# MainCyclomotion.net
KiCad netlist of a schematic drawn in Altium Designer
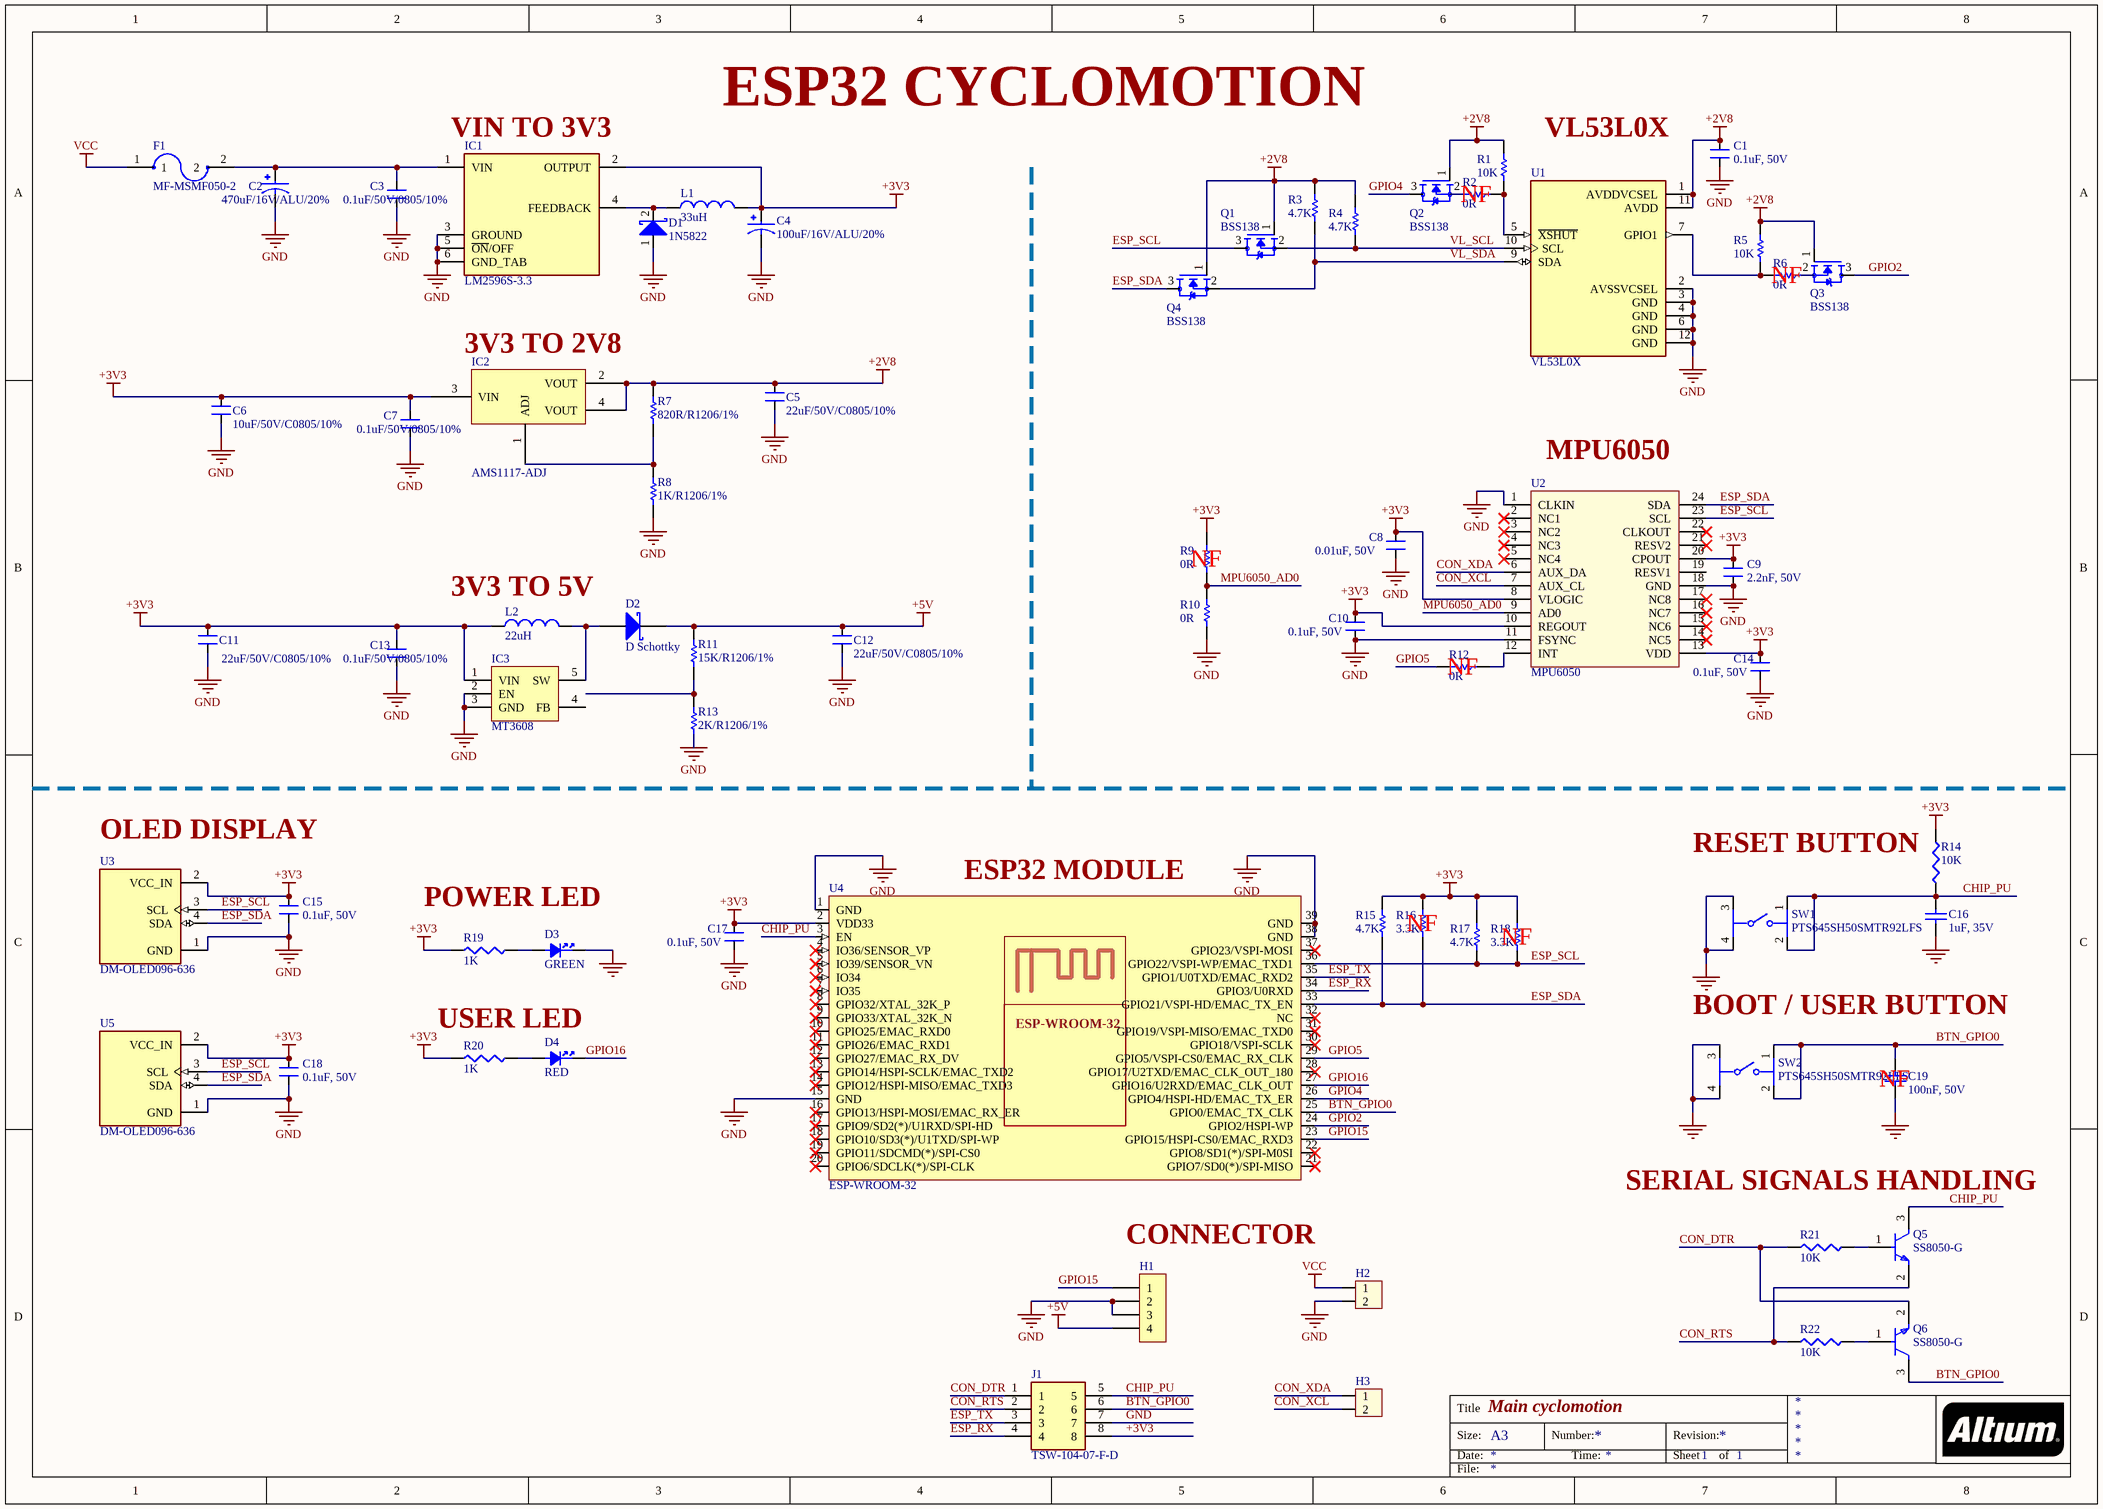
[diagram p0: MainCyclomotion.SchDoc]

(export (version "E")
  (design (tool "Eeschema 10.0.6"))
  (components
    (comp (ref "C1")
      (value "0.1uF, 50V")
      (footprint "CAP_CERA_C2012(CC0805INCH)")
      (description "CERAMIC CAP 0805")
      (libsource (lib "LPSON") (part "CAP CERA 0805"))
    )
    (comp (ref "C2")
      (value "470uF/16V/ALU/20%")
      (footprint "Cap_ALU_D_SMD")
      (libsource (lib "Schlib1") (part "Cap_ALU_D_SMD"))
    )
    (comp (ref "C3")
      (value "0.1uF/50V/0805/10%")
      (footprint "CAP_CERA_C2012(CC0805INCH)")
      (description "CERAMIC CAP 0805")
      (libsource (lib "LPSON") (part "CAP CERA 0805"))
    )
    (comp (ref "C4")
      (value "100uF/16V/ALU/20%")
      (footprint "Cap_ALU_E_SMD")
      (libsource (lib "Schlib1") (part "Cap_ALU_E_SMD"))
    )
    (comp (ref "C5")
      (value "22uF/50V/C0805/10%")
      (footprint "CAP_CERA_C2012(CC0805INCH)")
      (description "CERAMIC CAP 0805")
      (libsource (lib "Cyclomotion") (part "CAP CERA 0805"))
    )
    (comp (ref "C6")
      (value "10uF/50V/C0805/10%")
      (footprint "CAP_CERA_C2012(CC0805INCH)")
      (description "CERAMIC CAP 0805")
      (libsource (lib "Cyclomotion") (part "CAP CERA 0805"))
    )
    (comp (ref "C7")
      (value "0.1uF/50V/0805/10%")
      (footprint "CAP_CERA_C2012(CC0805INCH)")
      (description "CERAMIC CAP 0805")
      (libsource (lib "LPSON") (part "CAP CERA 0805"))
    )
    (comp (ref "C8")
      (value "0.01uF, 50V")
      (footprint "CAP_CERA_C2012(CC0805INCH)")
      (description "CERAMIC CAP 0805")
      (libsource (lib "LPSON") (part "CAP CERA 0805"))
    )
    (comp (ref "C9")
      (value "2.2nF, 50V")
      (footprint "CAP_CERA_C2012(CC0805INCH)")
      (description "CERAMIC CAP 0805")
      (libsource (lib "LPSON") (part "CAP CERA 0805"))
    )
    (comp (ref "C10")
      (value "0.1uF, 50V")
      (footprint "CAP_CERA_C2012(CC0805INCH)")
      (description "CERAMIC CAP 0805")
      (libsource (lib "LPSON") (part "CAP CERA 0805"))
    )
    (comp (ref "C11")
      (value "22uF/50V/C0805/10%")
      (footprint "CAP_CERA_C2012(CC0805INCH)")
      (description "CERAMIC CAP 0805")
      (libsource (lib "Cyclomotion") (part "CAP CERA 0805"))
    )
    (comp (ref "C12")
      (value "22uF/50V/C0805/10%")
      (footprint "CAP_CERA_C2012(CC0805INCH)")
      (description "CERAMIC CAP 0805")
      (libsource (lib "Cyclomotion") (part "CAP CERA 0805"))
    )
    (comp (ref "C13")
      (value "0.1uF/50V/0805/10%")
      (footprint "CAP_CERA_C2012(CC0805INCH)")
      (description "CERAMIC CAP 0805")
      (libsource (lib "LPSON") (part "CAP CERA 0805"))
    )
    (comp (ref "C14")
      (value "0.1uF, 50V")
      (footprint "CAP_CERA_C2012(CC0805INCH)")
      (description "CERAMIC CAP 0805")
      (libsource (lib "LPSON") (part "CAP CERA 0805"))
    )
    (comp (ref "C15")
      (value "0.1uF, 50V")
      (footprint "CAP_CERA_C2012(CC0805INCH)")
      (description "CERAMIC CAP 0805")
      (libsource (lib "LPSON") (part "CAP CERA 0805"))
    )
    (comp (ref "C16")
      (value "1uF, 35V")
      (footprint "CAPC1005X55N")
      (description "CAP CER 1UF 35V X5R 0402")
      (fields
        (field (name "MANUFACTURER") "Samsung")
        (field (name "MANUFACTURER PART NUMBER") "CL05A105KL5NRNC")
      )
      (libsource (lib "Schlib") (part "CL05A105KL5NRNC"))
    )
    (comp (ref "C17")
      (value "0.1uF, 50V")
      (footprint "CAP_CERA_C2012(CC0805INCH)")
      (description "CERAMIC CAP 0805")
      (libsource (lib "LPSON") (part "CAP CERA 0805"))
    )
    (comp (ref "C18")
      (value "0.1uF, 50V")
      (footprint "CAP_CERA_C2012(CC0805INCH)")
      (description "CERAMIC CAP 0805")
      (libsource (lib "LPSON") (part "CAP CERA 0805"))
    )
    (comp (ref "C19")
      (value "100nF, 50V")
      (footprint "CAPC1005X55N")
      (description "CAP CER 0.1UF 50V X7R 0402")
      (fields
        (field (name "MANUFACTURER") "Samsung")
        (field (name "MANUFACTURER PART NUMBER") "CL05B104KB54PNC")
      )
      (libsource (lib "Schlib") (part "CL05B104KB54PNC"))
    )
    (comp (ref "D1")
      (value "1N5822")
      (footprint "D_1N5822_DO201AD_THT")
      (description "Schottky Diode 3A 40V DO-201AD")
      (libsource (lib "LPSON") (part "1N5822"))
    )
    (comp (ref "D2")
      (value "D Schottky")
      (footprint "DIODE SMA")
      (description "Schottky Diode")
      (fields (field (name "PUBLISHER") "Altium Limited"))
      (libsource (lib "LPSON") (part "D Schottky"))
    )
    (comp (ref "D3")
      (value "GREEN")
      (footprint "LED0402G")
      (description "LED YLW-GRN 0402 SMD")
      (fields
        (field (name "MANUFACTURER") "Vishay")
        (field (name "MANUFACTURER PART NUMBER") "VLMG1500-GS08")
      )
      (libsource (lib "Schlib") (part "VLMG1500-GS08"))
    )
    (comp (ref "D4")
      (value "RED")
      (footprint "LED0402R")
      (description "LED RED 0402 SMD")
      (fields
        (field (name "MANUFACTURER") "Vishay")
        (field (name "MANUFACTURER PART NUMBER") "VLMS1500-GS08")
      )
      (libsource (lib "Schlib") (part "VLMS1500-GS08"))
    )
    (comp (ref "F1")
      (value "MF-MSMF050-2")
      (footprint "FUSM4632X85")
      (description "Polymeric PTC Resettable Fuse 15V 500 mA Ih Surface Mount 1812 (4532 Metric), Concave")
      (fields (field (name "MF") "Bourns"))
      (libsource (lib "Schlib1") (part "MF-MSMF050-2"))
    )
    (comp (ref "H1")
      (value "Header 4P 2.54 Duc Thang")
      (footprint "XH2.54M-4")
      (description "Cắm")
      (libsource (lib "Altium_Lib_by_KhueNguyenCreator") (part "Header 4P 2.54 Duc Thang"))
    )
    (comp (ref "H2")
      (value "Header 2P 2.54 Duc Thang")
      (footprint "XH2.54M-2")
      (description "Cắm")
      (libsource (lib "Altium_Lib_by_KhueNguyenCreator") (part "Header 2P 2.54 Duc Thang"))
    )
    (comp (ref "H3")
      (value "Header 2P 2.54 Duc Thang")
      (footprint "XH2.54M-2")
      (description "Cắm")
      (libsource (lib "Altium_Lib_by_KhueNguyenCreator") (part "Header 2P 2.54 Duc Thang"))
    )
    (comp (ref "IC1")
      (value "LM2596S-3.3")
      (footprint "TO170P1524X483-6N")
      (description "SIMPLE SWITCHER® 4.5V to 40V, 3A Low Component Count Step-Down Regulator")
      (libsource (lib "Schlib1") (part "LM2596S-3.3"))
    )
    (comp (ref "IC2")
      (value "AMS1117-ADJ")
      (footprint "SOT223")
      (description "Dán")
      (libsource (lib "Altium_Lib_by_KhueNguyenCreator") (part "AMS1117 SMD"))
    )
    (comp (ref "IC3")
      (value "MT3608")
      (footprint "SOT23-5")
      (description "The MT3608 is a constant frequency, 6-pin SOT23\r\ncurrent mode step-up converter")
      (fields (field (name "MANUFACTURER") "AEROSEMI"))
      (libsource (lib "MainCyclomotion") (part "MT3608"))
    )
    (comp (ref "J1")
      (value "TSW-104-07-F-D")
      (footprint "SAMTEC_TSW-104-07-F-D")
      (libsource (lib "MainCyclomotion_1") (part "TSW-104-07-F-D"))
    )
    (comp (ref "L1")
      (value "33uH")
      (footprint "L_CDRH17_33uH_SMD")
      (description "Inductor")
      (fields (field (name "PUBLISHER") "Altium Limited"))
      (libsource (lib "MainCyclomotion") (part "Inductor"))
    )
    (comp (ref "L2")
      (value "22uH")
      (footprint "L_CDRH104_22uH_SMD")
      (description "Inductor")
      (fields (field (name "PUBLISHER") "Altium Limited"))
      (libsource (lib "LPSON") (part "Inductor"))
    )
    (comp (ref "Q1")
      (value "BSS138")
      (footprint "SOT95P240X111-3N")
      (description "N-Channel 50 V 220mA (Ta) 350mW (Ta) Surface Mount SOT-23-3")
      (libsource (lib "MainCyclomotion_1") (part "BSS138"))
    )
    (comp (ref "Q2")
      (value "BSS138")
      (footprint "SOT95P240X111-3N")
      (description "N-Channel 50 V 220mA (Ta) 350mW (Ta) Surface Mount SOT-23-3")
      (libsource (lib "MainCyclomotion_1") (part "BSS138"))
    )
    (comp (ref "Q3")
      (value "BSS138")
      (footprint "SOT95P240X111-3N")
      (description "N-Channel 50 V 220mA (Ta) 350mW (Ta) Surface Mount SOT-23-3")
      (libsource (lib "MainCyclomotion_1") (part "BSS138"))
    )
    (comp (ref "Q4")
      (value "BSS138")
      (footprint "SOT95P240X111-3N")
      (description "N-Channel 50 V 220mA (Ta) 350mW (Ta) Surface Mount SOT-23-3")
      (libsource (lib "MainCyclomotion_1") (part "BSS138"))
    )
    (comp (ref "Q5")
      (value "SS8050-G")
      (footprint "FP-SS8050-G-IPC_B")
      (description "TRANS NPN 25V 1.5A SOT23-3")
      (fields (field (name "MANUFACTURER") "Comchip") (field (name "LCSC PART NUMBER") "C164886"))
      (libsource (lib "Schlib") (part "SS8050-G"))
    )
    (comp (ref "Q6")
      (value "SS8050-G")
      (footprint "FP-SS8050-G-IPC_B")
      (description "TRANS NPN 25V 1.5A SOT23-3")
      (fields (field (name "MANUFACTURER") "Comchip") (field (name "LCSC PART NUMBER") "C164886"))
      (libsource (lib "Schlib") (part "SS8050-G"))
    )
    (comp (ref "R1")
      (value "10K")
      (footprint "Res 1206 SMD")
      (description "RES SMD 10K OHM 1% 1206")
      (fields
        (field (name "MANUFACTURER") "Yageo")
        (field (name "MANUFACTURER PART NUMBER") "RC1206FR-075R1L")
      )
      (libsource (lib "Cyclomotion") (part "RES-1206"))
    )
    (comp (ref "R2")
      (value "0R")
      (footprint "Res 1206 SMD")
      (description "RES SMD 10K OHM 1% 1206")
      (fields
        (field (name "MANUFACTURER") "Yageo")
        (field (name "MANUFACTURER PART NUMBER") "RC1206FR-075R1L")
      )
      (libsource (lib "Cyclomotion") (part "RES-1206"))
    )
    (comp (ref "R3")
      (value "4.7K")
      (footprint "Res 1206 SMD")
      (description "RES SMD 10K OHM 1% 1206")
      (fields
        (field (name "MANUFACTURER") "Yageo")
        (field (name "MANUFACTURER PART NUMBER") "RC1206FR-075R1L")
      )
      (libsource (lib "Cyclomotion") (part "RES-1206"))
    )
    (comp (ref "R4")
      (value "4.7K")
      (footprint "Res 1206 SMD")
      (description "RES SMD 10K OHM 1% 1206")
      (fields
        (field (name "MANUFACTURER") "Yageo")
        (field (name "MANUFACTURER PART NUMBER") "RC1206FR-075R1L")
      )
      (libsource (lib "Cyclomotion") (part "RES-1206"))
    )
    (comp (ref "R5")
      (value "10K")
      (footprint "Res 1206 SMD")
      (description "RES SMD 10K OHM 1% 1206")
      (fields
        (field (name "MANUFACTURER") "Yageo")
        (field (name "MANUFACTURER PART NUMBER") "RC1206FR-075R1L")
      )
      (libsource (lib "Cyclomotion") (part "RES-1206"))
    )
    (comp (ref "R6")
      (value "0R")
      (footprint "Res 1206 SMD")
      (description "RES SMD 10K OHM 1% 1206")
      (fields
        (field (name "MANUFACTURER") "Yageo")
        (field (name "MANUFACTURER PART NUMBER") "RC1206FR-075R1L")
      )
      (libsource (lib "Cyclomotion") (part "RES-1206"))
    )
    (comp (ref "R7")
      (value "820R/R1206/1%")
      (footprint "Res 1206 SMD")
      (description "RES SMD 10K OHM 1% 1206")
      (fields
        (field (name "MANUFACTURER") "Yageo")
        (field (name "MANUFACTURER PART NUMBER") "RC1206FR-075R1L")
      )
      (libsource (lib "Cyclomotion") (part "RES-1206"))
    )
    (comp (ref "R8")
      (value "1K/R1206/1%")
      (footprint "Res 1206 SMD")
      (description "RES SMD 10K OHM 1% 1206")
      (fields
        (field (name "MANUFACTURER") "Yageo")
        (field (name "MANUFACTURER PART NUMBER") "RC1206FR-075R1L")
      )
      (libsource (lib "Cyclomotion") (part "RES-1206"))
    )
    (comp (ref "R9")
      (value "0R")
      (footprint "Res 1206 SMD")
      (description "RES SMD 10K OHM 1% 1206")
      (fields
        (field (name "MANUFACTURER") "Yageo")
        (field (name "MANUFACTURER PART NUMBER") "RC1206FR-075R1L")
      )
      (libsource (lib "Cyclomotion") (part "RES-1206"))
    )
    (comp (ref "R10")
      (value "0R")
      (footprint "Res 1206 SMD")
      (description "RES SMD 10K OHM 1% 1206")
      (fields
        (field (name "MANUFACTURER") "Yageo")
        (field (name "MANUFACTURER PART NUMBER") "RC1206FR-075R1L")
      )
      (libsource (lib "Cyclomotion") (part "RES-1206"))
    )
    (comp (ref "R11")
      (value "15K/R1206/1%")
      (footprint "Res 1206 SMD")
      (description "RES SMD 10K OHM 1% 1206")
      (fields
        (field (name "MANUFACTURER") "Yageo")
        (field (name "MANUFACTURER PART NUMBER") "RC1206FR-075R1L")
      )
      (libsource (lib "Cyclomotion") (part "RES-1206"))
    )
    (comp (ref "R12")
      (value "0R")
      (footprint "Res 1206 SMD")
      (description "RES SMD 10K OHM 1% 1206")
      (fields
        (field (name "MANUFACTURER") "Yageo")
        (field (name "MANUFACTURER PART NUMBER") "RC1206FR-075R1L")
      )
      (libsource (lib "Cyclomotion") (part "RES-1206"))
    )
    (comp (ref "R13")
      (value "2K/R1206/1%")
      (footprint "Res 1206 SMD")
      (description "RES SMD 10K OHM 1% 1206")
      (fields
        (field (name "MANUFACTURER") "Yageo")
        (field (name "MANUFACTURER PART NUMBER") "RC1206FR-075R1L")
      )
      (libsource (lib "Cyclomotion") (part "RES-1206"))
    )
    (comp (ref "R14")
      (value "10K")
      (footprint "RESC1005X37N")
      (description "RES SMD 10K OHM 1% 1/16W 0402")
      (fields
        (field (name "MANUFACTURER") "Yageo")
        (field (name "MANUFACTURER PART NUMBER") "AC0402FR-0710KL")
      )
      (libsource (lib "Schlib") (part "AC0402FR-0710KL"))
    )
    (comp (ref "R15")
      (value "4.7K")
      (footprint "Res 1206 SMD")
      (description "RES SMD 10K OHM 1% 1206")
      (fields
        (field (name "MANUFACTURER") "Yageo")
        (field (name "MANUFACTURER PART NUMBER") "RC1206FR-075R1L")
      )
      (libsource (lib "Cyclomotion") (part "RES-1206"))
    )
    (comp (ref "R16")
      (value "3.3K")
      (footprint "Res 1206 SMD")
      (description "RES SMD 10K OHM 1% 1206")
      (fields
        (field (name "MANUFACTURER") "Yageo")
        (field (name "MANUFACTURER PART NUMBER") "RC1206FR-075R1L")
      )
      (libsource (lib "Cyclomotion") (part "RES-1206"))
    )
    (comp (ref "R17")
      (value "4.7K")
      (footprint "Res 1206 SMD")
      (description "RES SMD 10K OHM 1% 1206")
      (fields
        (field (name "MANUFACTURER") "Yageo")
        (field (name "MANUFACTURER PART NUMBER") "RC1206FR-075R1L")
      )
      (libsource (lib "Cyclomotion") (part "RES-1206"))
    )
    (comp (ref "R18")
      (value "3.3K")
      (footprint "Res 1206 SMD")
      (description "RES SMD 10K OHM 1% 1206")
      (fields
        (field (name "MANUFACTURER") "Yageo")
        (field (name "MANUFACTURER PART NUMBER") "RC1206FR-075R1L")
      )
      (libsource (lib "Cyclomotion") (part "RES-1206"))
    )
    (comp (ref "R19")
      (value "1K")
      (footprint "RESC1005X37N")
      (description "RES 1K OHM 1% 1/16W 0402")
      (fields
        (field (name "MANUFACTURER") "Yageo")
        (field (name "MANUFACTURER PART NUMBER") "RC0402FR-071KL")
      )
      (libsource (lib "Schlib") (part "RC0402FR-071KL"))
    )
    (comp (ref "R20")
      (value "1K")
      (footprint "RESC1005X37N")
      (description "RES 1K OHM 1% 1/16W 0402")
      (fields
        (field (name "MANUFACTURER") "Yageo")
        (field (name "MANUFACTURER PART NUMBER") "RC0402FR-071KL")
      )
      (libsource (lib "Schlib") (part "RC0402FR-071KL"))
    )
    (comp (ref "R21")
      (value "10K")
      (footprint "RESC1005X37N")
      (description "RES SMD 10K OHM 1% 1/16W 0402")
      (fields
        (field (name "MANUFACTURER") "Yageo")
        (field (name "MANUFACTURER PART NUMBER") "AC0402FR-0710KL")
      )
      (libsource (lib "Schlib") (part "AC0402FR-0710KL"))
    )
    (comp (ref "R22")
      (value "10K")
      (footprint "RESC1005X37N")
      (description "RES SMD 10K OHM 1% 1/16W 0402")
      (fields
        (field (name "MANUFACTURER") "Yageo")
        (field (name "MANUFACTURER PART NUMBER") "AC0402FR-0710KL")
      )
      (libsource (lib "Schlib") (part "AC0402FR-0710KL"))
    )
    (comp (ref "SW1")
      (value "PTS645SH50SMTR92LFS")
      (footprint "FP-PTS645SH50SMTR92LFS-MFG")
      (description "SWITCH TACTILE SPST-NO 0.05A 12V")
      (fields (field (name "MANUFACTURER") "ITT C&K") (field (name "LCSC PART NUMBER") "C221869"))
      (libsource (lib "Schlib") (part "PTS645SH50SMTR92LFS"))
    )
    (comp (ref "SW2")
      (value "PTS645SH50SMTR92LFS")
      (footprint "FP-PTS645SH50SMTR92LFS-MFG")
      (description "SWITCH TACTILE SPST-NO 0.05A 12V")
      (fields (field (name "MANUFACTURER") "ITT C&K") (field (name "LCSC PART NUMBER") "C221869"))
      (libsource (lib "Schlib") (part "PTS645SH50SMTR92LFS"))
    )
    (comp (ref "U1")
      (value "VL53L0X")
      (footprint "SENSOR_VL53L0X")
      (description "VL53L0X - Light, 3D Time-of-Flight _ToF_ Sensor Evaluation Board")
      (fields (field (name "MF") "STMicroelectronics"))
      (libsource (lib "MainCyclomotion_1") (part "VL53L0X"))
    )
    (comp (ref "U2")
      (value "MPU6050")
      (footprint "14# MPU -6050")
      (libsource (lib "MainCyclomotion_1") (part "MPU6050"))
    )
    (comp (ref "U3")
      (value "DM-OLED096-636")
      (footprint "MODULE_DM-OLED096-636")
      (description "0.96â€ 128 X 64 MONOCHROME GRAPHIC OLED DISPLAY MODULE - I2C")
      (fields (field (name "MF") "Display Module"))
      (libsource (lib "DM-OLED096-636") (part "DM-OLED096-636"))
    )
    (comp (ref "U4")
      (value "ESP-WROOM-32")
      (footprint "ESP32 WROOM")
      (libsource (lib "LPSON") (part "ESP-WROOM-32"))
    )
    (comp (ref "U5")
      (value "DM-OLED096-636")
      (footprint "MODULE_DM-OLED096-636")
      (description "0.96â€ 128 X 64 MONOCHROME GRAPHIC OLED DISPLAY MODULE - I2C")
      (fields (field (name "MF") "Display Module"))
      (libsource (lib "DM-OLED096-636") (part "DM-OLED096-636"))
    )
  )
  (nets
    (net (code "1") (name "+2V8") (class "Default")
      (node (ref "C1") (pin "1") (pinfunction "1_1") (pintype "passive"))
      (node (ref "C5") (pin "2") (pinfunction "2_2") (pintype "passive"))
      (node (ref "IC2") (pin "2") (pinfunction "VOUT_2") (pintype "passive"))
      (node (ref "IC2") (pin "4") (pinfunction "VOUT_4") (pintype "passive"))
      (node (ref "Q1") (pin "1") (pinfunction "G_1") (pintype "passive"))
      (node (ref "Q2") (pin "1") (pinfunction "G_1") (pintype "passive"))
      (node (ref "Q3") (pin "1") (pinfunction "G_1") (pintype "passive"))
      (node (ref "Q4") (pin "1") (pinfunction "G_1") (pintype "passive"))
      (node (ref "R1") (pin "2") (pinfunction "2_2") (pintype "passive"))
      (node (ref "R3") (pin "2") (pinfunction "2_2") (pintype "passive"))
      (node (ref "R4") (pin "2") (pinfunction "2_2") (pintype "passive"))
      (node (ref "R5") (pin "2") (pinfunction "2_2") (pintype "passive"))
      (node (ref "R7") (pin "1") (pinfunction "1_1") (pintype "passive"))
      (node (ref "U1") (pin "1") (pinfunction "AVDDVCSEL_1") (pintype "power_in"))
      (node (ref "U1") (pin "11") (pinfunction "AVDD_11") (pintype "power_in"))
    )
    (net (code "2") (name "+3V3") (class "Default")
      (node (ref "C10") (pin "1") (pinfunction "1_1") (pintype "passive"))
      (node (ref "C11") (pin "2") (pinfunction "2_2") (pintype "passive"))
      (node (ref "C13") (pin "1") (pinfunction "1_1") (pintype "passive"))
      (node (ref "C14") (pin "1") (pinfunction "1_1") (pintype "passive"))
      (node (ref "C15") (pin "1") (pinfunction "1_1") (pintype "passive"))
      (node (ref "C17") (pin "1") (pinfunction "1_1") (pintype "passive"))
      (node (ref "C18") (pin "1") (pinfunction "1_1") (pintype "passive"))
      (node (ref "C4") (pin "1") (pinfunction "1_1") (pintype "passive"))
      (node (ref "C6") (pin "2") (pinfunction "2_2") (pintype "passive"))
      (node (ref "C7") (pin "1") (pinfunction "1_1") (pintype "passive"))
      (node (ref "C8") (pin "1") (pinfunction "1_1") (pintype "passive"))
      (node (ref "C9") (pin "1") (pinfunction "1_1") (pintype "passive"))
      (node (ref "IC1") (pin "2") (pinfunction "OUTPUT_2") (pintype "passive"))
      (node (ref "IC2") (pin "3") (pinfunction "VIN_3") (pintype "passive"))
      (node (ref "IC3") (pin "1") (pinfunction "VIN_1") (pintype "passive"))
      (node (ref "J1") (pin "8") (pinfunction "8_8") (pintype "passive"))
      (node (ref "L1") (pin "2") (pinfunction "2_2") (pintype "passive"))
      (node (ref "L2") (pin "1") (pinfunction "1_1") (pintype "passive"))
      (node (ref "R14") (pin "2") (pinfunction "2_2") (pintype "passive"))
      (node (ref "R15") (pin "2") (pinfunction "2_2") (pintype "passive"))
      (node (ref "R16") (pin "2") (pinfunction "2_2") (pintype "passive"))
      (node (ref "R17") (pin "2") (pinfunction "2_2") (pintype "passive"))
      (node (ref "R18") (pin "2") (pinfunction "2_2") (pintype "passive"))
      (node (ref "R19") (pin "2") (pinfunction "2_2") (pintype "passive"))
      (node (ref "R20") (pin "2") (pinfunction "2_2") (pintype "passive"))
      (node (ref "R9") (pin "2") (pinfunction "2_2") (pintype "passive"))
      (node (ref "U2") (pin "10") (pinfunction "REGOUT_10") (pintype "passive"))
      (node (ref "U2") (pin "13") (pinfunction "VDD_13") (pintype "passive"))
      (node (ref "U2") (pin "20") (pinfunction "CPOUT_20") (pintype "passive"))
      (node (ref "U2") (pin "8") (pinfunction "VLOGIC_8") (pintype "passive"))
      (node (ref "U3") (pin "2") (pinfunction "VCC_IN_2") (pintype "power_in"))
      (node (ref "U4") (pin "2") (pinfunction "VDD33_2") (pintype "passive"))
      (node (ref "U5") (pin "2") (pinfunction "VCC_IN_2") (pintype "power_in"))
    )
    (net (code "3") (name "+5V") (class "Default")
      (node (ref "C12") (pin "2") (pinfunction "2_2") (pintype "passive"))
      (node (ref "D2") (pin "2") (pinfunction "K_2") (pintype "passive"))
      (node (ref "H1") (pin "4") (pinfunction "4_4") (pintype "passive"))
      (node (ref "R11") (pin "1") (pinfunction "1_1") (pintype "passive"))
    )
    (net (code "4") (name "/BTN_GPIO0") (class "Default")
      (node (ref "C19") (pin "2") (pinfunction "2_2") (pintype "passive"))
      (node (ref "J1") (pin "6") (pinfunction "6_6") (pintype "passive"))
      (node (ref "Q6") (pin "3") (pinfunction "C_3") (pintype "passive"))
      (node (ref "SW2") (pin "1") (pinfunction "1_1") (pintype "passive"))
      (node (ref "SW2") (pin "2") (pinfunction "2_2") (pintype "passive"))
      (node (ref "U4") (pin "25") (pinfunction "GPIO0/EMAC_TX_CLK_25") (pintype "passive"))
    )
    (net (code "5") (name "/CHIP_PU") (class "Default")
      (node (ref "C16") (pin "2") (pinfunction "2_2") (pintype "passive"))
      (node (ref "J1") (pin "5") (pinfunction "5_5") (pintype "passive"))
      (node (ref "Q5") (pin "3") (pinfunction "C_3") (pintype "passive"))
      (node (ref "R14") (pin "1") (pinfunction "1_1") (pintype "passive"))
      (node (ref "SW1") (pin "1") (pinfunction "1_1") (pintype "passive"))
      (node (ref "SW1") (pin "2") (pinfunction "2_2") (pintype "passive"))
      (node (ref "U4") (pin "3") (pinfunction "EN_3") (pintype "input"))
    )
    (net (code "6") (name "/CON_DTR") (class "Default")
      (node (ref "J1") (pin "1") (pinfunction "1_1") (pintype "passive"))
      (node (ref "Q6") (pin "2") (pinfunction "E_2") (pintype "passive"))
      (node (ref "R21") (pin "1") (pinfunction "1_1") (pintype "passive"))
    )
    (net (code "7") (name "/CON_RTS") (class "Default")
      (node (ref "J1") (pin "2") (pinfunction "2_2") (pintype "passive"))
      (node (ref "Q5") (pin "2") (pinfunction "E_2") (pintype "passive"))
      (node (ref "R22") (pin "1") (pinfunction "1_1") (pintype "passive"))
    )
    (net (code "8") (name "/CON_XCL") (class "Default")
      (node (ref "H3") (pin "2") (pinfunction "2_2") (pintype "passive"))
      (node (ref "U2") (pin "7") (pinfunction "AUX_CL_7") (pintype "passive"))
    )
    (net (code "9") (name "/CON_XDA") (class "Default")
      (node (ref "H3") (pin "1") (pinfunction "1_1") (pintype "passive"))
      (node (ref "U2") (pin "6") (pinfunction "AUX_DA_6") (pintype "passive"))
    )
    (net (code "10") (name "/ESP_RX") (class "Default")
      (node (ref "J1") (pin "4") (pinfunction "4_4") (pintype "passive"))
      (node (ref "U4") (pin "34") (pinfunction "GPIO3/U0RXD_34") (pintype "passive"))
    )
    (net (code "11") (name "/ESP_SCL") (class "Default")
      (node (ref "Q1") (pin "3") (pinfunction "D_3") (pintype "passive"))
      (node (ref "R17") (pin "1") (pinfunction "1_1") (pintype "passive"))
      (node (ref "R18") (pin "1") (pinfunction "1_1") (pintype "passive"))
      (node (ref "U2") (pin "23") (pinfunction "SCL_23") (pintype "passive"))
      (node (ref "U3") (pin "3") (pinfunction "SCL_3") (pintype "input"))
      (node (ref "U4") (pin "36") (pinfunction "GPIO22/VSPI-WP/EMAC_TXD1_36") (pintype "passive"))
      (node (ref "U5") (pin "3") (pinfunction "SCL_3") (pintype "input"))
    )
    (net (code "12") (name "/ESP_SDA") (class "Default")
      (node (ref "Q4") (pin "3") (pinfunction "D_3") (pintype "passive"))
      (node (ref "R15") (pin "1") (pinfunction "1_1") (pintype "passive"))
      (node (ref "R16") (pin "1") (pinfunction "1_1") (pintype "passive"))
      (node (ref "U2") (pin "24") (pinfunction "SDA_24") (pintype "passive"))
      (node (ref "U3") (pin "4") (pinfunction "SDA_4") (pintype "bidirectional"))
      (node (ref "U4") (pin "33") (pinfunction "GPIO21/VSPI-HD/EMAC_TX_EN_33") (pintype "passive"))
      (node (ref "U5") (pin "4") (pinfunction "SDA_4") (pintype "bidirectional"))
    )
    (net (code "13") (name "/ESP_TX") (class "Default")
      (node (ref "J1") (pin "3") (pinfunction "3_3") (pintype "passive"))
      (node (ref "U4") (pin "35") (pinfunction "GPIO1/U0TXD/EMAC_RXD2_35") (pintype "passive"))
    )
    (net (code "14") (name "/GPIO2") (class "Default")
      (node (ref "Q3") (pin "3") (pinfunction "D_3") (pintype "passive"))
      (node (ref "U4") (pin "24") (pinfunction "GPIO2/HSPI-WP_24") (pintype "passive"))
    )
    (net (code "15") (name "/GPIO4") (class "Default")
      (node (ref "Q2") (pin "3") (pinfunction "D_3") (pintype "passive"))
      (node (ref "U4") (pin "26") (pinfunction "GPIO4/HSPI-HD/EMAC_TX_ER_26") (pintype "passive"))
    )
    (net (code "16") (name "/GPIO5") (class "Default")
      (node (ref "R12") (pin "2") (pinfunction "2_2") (pintype "passive"))
      (node (ref "U4") (pin "29") (pinfunction "GPIO5/VSPI-CS0/EMAC_RX_CLK_29") (pintype "passive"))
    )
    (net (code "17") (name "/GPIO15") (class "Default")
      (node (ref "H1") (pin "1") (pinfunction "1_1") (pintype "passive"))
      (node (ref "U4") (pin "23") (pinfunction "GPIO15/HSPI-CS0/EMAC_RXD3_23") (pintype "passive"))
    )
    (net (code "18") (name "/GPIO16") (class "Default")
      (node (ref "D4") (pin "1") (pinfunction "1_1") (pintype "passive"))
      (node (ref "U4") (pin "27") (pinfunction "GPIO16/U2RXD/EMAC_CLK_OUT_27") (pintype "passive"))
    )
    (net (code "19") (name "/MPU6050_AD0") (class "Default")
      (node (ref "R10") (pin "2") (pinfunction "2_2") (pintype "passive"))
      (node (ref "R9") (pin "1") (pinfunction "1_1") (pintype "passive"))
      (node (ref "U2") (pin "9") (pinfunction "AD0_9") (pintype "passive"))
    )
    (net (code "20") (name "/VL_SCL") (class "Default")
      (node (ref "Q1") (pin "2") (pinfunction "S_2") (pintype "passive"))
      (node (ref "R4") (pin "1") (pinfunction "1_1") (pintype "passive"))
      (node (ref "U1") (pin "10") (pinfunction "SCL_10") (pintype "input"))
    )
    (net (code "21") (name "/VL_SDA") (class "Default")
      (node (ref "Q4") (pin "2") (pinfunction "S_2") (pintype "passive"))
      (node (ref "R3") (pin "1") (pinfunction "1_1") (pintype "passive"))
      (node (ref "U1") (pin "9") (pinfunction "SDA_9") (pintype "bidirectional"))
    )
    (net (code "22") (name "GND") (class "Default")
      (node (ref "C1") (pin "2") (pinfunction "2_2") (pintype "passive"))
      (node (ref "C10") (pin "2") (pinfunction "2_2") (pintype "passive"))
      (node (ref "C11") (pin "1") (pinfunction "1_1") (pintype "passive"))
      (node (ref "C12") (pin "1") (pinfunction "1_1") (pintype "passive"))
      (node (ref "C13") (pin "2") (pinfunction "2_2") (pintype "passive"))
      (node (ref "C14") (pin "2") (pinfunction "2_2") (pintype "passive"))
      (node (ref "C15") (pin "2") (pinfunction "2_2") (pintype "passive"))
      (node (ref "C16") (pin "1") (pinfunction "1_1") (pintype "passive"))
      (node (ref "C17") (pin "2") (pinfunction "2_2") (pintype "passive"))
      (node (ref "C18") (pin "2") (pinfunction "2_2") (pintype "passive"))
      (node (ref "C19") (pin "1") (pinfunction "1_1") (pintype "passive"))
      (node (ref "C2") (pin "2") (pinfunction "2_2") (pintype "passive"))
      (node (ref "C3") (pin "2") (pinfunction "2_2") (pintype "passive"))
      (node (ref "C4") (pin "2") (pinfunction "2_2") (pintype "passive"))
      (node (ref "C5") (pin "1") (pinfunction "1_1") (pintype "passive"))
      (node (ref "C6") (pin "1") (pinfunction "1_1") (pintype "passive"))
      (node (ref "C7") (pin "2") (pinfunction "2_2") (pintype "passive"))
      (node (ref "C8") (pin "2") (pinfunction "2_2") (pintype "passive"))
      (node (ref "C9") (pin "2") (pinfunction "2_2") (pintype "passive"))
      (node (ref "D1") (pin "1") (pinfunction "A_1") (pintype "passive"))
      (node (ref "D3") (pin "1") (pinfunction "1_1") (pintype "passive"))
      (node (ref "H1") (pin "2") (pinfunction "2_2") (pintype "passive"))
      (node (ref "H1") (pin "3") (pinfunction "3_3") (pintype "passive"))
      (node (ref "H2") (pin "2") (pinfunction "2_2") (pintype "passive"))
      (node (ref "IC1") (pin "3") (pinfunction "GROUND_3") (pintype "power_in"))
      (node (ref "IC1") (pin "5") (pinfunction "~{ON}/OFF_5") (pintype "passive"))
      (node (ref "IC1") (pin "6") (pinfunction "GND_TAB_6") (pintype "power_in"))
      (node (ref "IC3") (pin "2") (pinfunction "EN_2") (pintype "passive"))
      (node (ref "IC3") (pin "3") (pinfunction "GND_3") (pintype "passive"))
      (node (ref "J1") (pin "7") (pinfunction "7_7") (pintype "passive"))
      (node (ref "R10") (pin "1") (pinfunction "1_1") (pintype "passive"))
      (node (ref "R13") (pin "2") (pinfunction "2_2") (pintype "passive"))
      (node (ref "R8") (pin "2") (pinfunction "2_2") (pintype "passive"))
      (node (ref "SW1") (pin "3") (pinfunction "3_3") (pintype "passive"))
      (node (ref "SW1") (pin "4") (pinfunction "4_4") (pintype "passive"))
      (node (ref "SW2") (pin "3") (pinfunction "3_3") (pintype "passive"))
      (node (ref "SW2") (pin "4") (pinfunction "4_4") (pintype "passive"))
      (node (ref "U1") (pin "12") (pinfunction "GND_12") (pintype "power_in"))
      (node (ref "U1") (pin "2") (pinfunction "AVSSVCSEL_2") (pintype "power_in"))
      (node (ref "U1") (pin "3") (pinfunction "GND_3") (pintype "power_in"))
      (node (ref "U1") (pin "4") (pinfunction "GND_4") (pintype "power_in"))
      (node (ref "U1") (pin "6") (pinfunction "GND_6") (pintype "power_in"))
      (node (ref "U2") (pin "1") (pinfunction "CLKIN_1") (pintype "passive"))
      (node (ref "U2") (pin "11") (pinfunction "FSYNC_11") (pintype "passive"))
      (node (ref "U2") (pin "18") (pinfunction "GND_18") (pintype "passive"))
      (node (ref "U3") (pin "1") (pinfunction "GND_1") (pintype "power_in"))
      (node (ref "U4") (pin "1") (pinfunction "GND_1") (pintype "passive"))
      (node (ref "U4") (pin "15") (pinfunction "GND_15") (pintype "passive"))
      (node (ref "U4") (pin "38") (pinfunction "GND_38") (pintype "passive"))
      (node (ref "U4") (pin "39") (pinfunction "GND_39") (pintype "passive"))
      (node (ref "U5") (pin "1") (pinfunction "GND_1") (pintype "power_in"))
    )
    (net (code "23") (name "Net-(D1-K)") (class "Default")
      (node (ref "D1") (pin "2") (pinfunction "K_2") (pintype "passive"))
      (node (ref "IC1") (pin "4") (pinfunction "FEEDBACK_4") (pintype "passive"))
      (node (ref "L1") (pin "1") (pinfunction "1_1") (pintype "passive"))
    )
    (net (code "24") (name "Net-(D2-A)") (class "Default")
      (node (ref "D2") (pin "1") (pinfunction "A_1") (pintype "passive"))
      (node (ref "IC3") (pin "5") (pinfunction "SW_5") (pintype "passive"))
      (node (ref "L2") (pin "2") (pinfunction "2_2") (pintype "passive"))
    )
    (net (code "25") (name "Net-(D3-Pad2)") (class "Default")
      (node (ref "D3") (pin "2") (pinfunction "2_2") (pintype "passive"))
      (node (ref "R19") (pin "1") (pinfunction "1_1") (pintype "passive"))
    )
    (net (code "26") (name "Net-(D4-Pad2)") (class "Default")
      (node (ref "D4") (pin "2") (pinfunction "2_2") (pintype "passive"))
      (node (ref "R20") (pin "1") (pinfunction "1_1") (pintype "passive"))
    )
    (net (code "27") (name "Net-(IC1-VIN)") (class "Default")
      (node (ref "C2") (pin "1") (pinfunction "1_1") (pintype "passive"))
      (node (ref "C3") (pin "1") (pinfunction "1_1") (pintype "passive"))
      (node (ref "F1") (pin "2") (pinfunction "2_2") (pintype "passive"))
      (node (ref "IC1") (pin "1") (pinfunction "VIN_1") (pintype "passive"))
    )
    (net (code "28") (name "Net-(IC2-ADJ)") (class "Default")
      (node (ref "IC2") (pin "1") (pinfunction "ADJ_1") (pintype "passive"))
      (node (ref "R7") (pin "2") (pinfunction "2_2") (pintype "passive"))
      (node (ref "R8") (pin "1") (pinfunction "1_1") (pintype "passive"))
    )
    (net (code "29") (name "Net-(Q2-S)") (class "Default")
      (node (ref "Q2") (pin "2") (pinfunction "S_2") (pintype "passive"))
      (node (ref "R2") (pin "2") (pinfunction "2_2") (pintype "passive"))
    )
    (net (code "30") (name "Net-(Q3-S)") (class "Default")
      (node (ref "Q3") (pin "2") (pinfunction "S_2") (pintype "passive"))
      (node (ref "R6") (pin "1") (pinfunction "1_1") (pintype "passive"))
    )
    (net (code "31") (name "Net-(Q5-B)") (class "Default")
      (node (ref "Q5") (pin "1") (pinfunction "B_1") (pintype "passive"))
      (node (ref "R21") (pin "2") (pinfunction "2_2") (pintype "passive"))
    )
    (net (code "32") (name "Net-(Q6-B)") (class "Default")
      (node (ref "Q6") (pin "1") (pinfunction "B_1") (pintype "passive"))
      (node (ref "R22") (pin "2") (pinfunction "2_2") (pintype "passive"))
    )
    (net (code "33") (name "Net-(R11-Pad2)") (class "Default")
      (node (ref "R11") (pin "2") (pinfunction "2_2") (pintype "passive"))
      (node (ref "R13") (pin "1") (pinfunction "1_1") (pintype "passive"))
    )
    (net (code "34") (name "Net-(U1-GPIO1)") (class "Default")
      (node (ref "R5") (pin "1") (pinfunction "1_1") (pintype "passive"))
      (node (ref "R6") (pin "2") (pinfunction "2_2") (pintype "passive"))
      (node (ref "U1") (pin "7") (pinfunction "GPIO1_7") (pintype "output"))
    )
    (net (code "35") (name "Net-(U1-~{XSHUT})") (class "Default")
      (node (ref "R1") (pin "1") (pinfunction "1_1") (pintype "passive"))
      (node (ref "R2") (pin "1") (pinfunction "1_1") (pintype "passive"))
      (node (ref "U1") (pin "5") (pinfunction "~{XSHUT}_5") (pintype "input"))
    )
    (net (code "36") (name "Net-(U2-INT)") (class "Default")
      (node (ref "R12") (pin "1") (pinfunction "1_1") (pintype "passive"))
      (node (ref "U2") (pin "12") (pinfunction "INT_12") (pintype "passive"))
    )
    (net (code "37") (name "VCC") (class "Default")
      (node (ref "F1") (pin "1") (pinfunction "1_1") (pintype "passive"))
      (node (ref "H2") (pin "1") (pinfunction "1_1") (pintype "passive"))
    )
    (net (code "38") (name "unconnected-(IC3-FB-Pad4)") (class "Default")
      (node (ref "IC3") (pin "4") (pinfunction "FB_4") (pintype "passive"))
    )
    (net (code "39") (name "unconnected-(U2-CLKOUT-Pad22)") (class "Default")
      (node (ref "U2") (pin "22") (pinfunction "CLKOUT_22") (pintype "passive+no_connect"))
    )
    (net (code "40") (name "unconnected-(U2-NC1-Pad2)") (class "Default")
      (node (ref "U2") (pin "2") (pinfunction "NC1_2") (pintype "passive+no_connect"))
    )
    (net (code "41") (name "unconnected-(U2-NC2-Pad3)") (class "Default")
      (node (ref "U2") (pin "3") (pinfunction "NC2_3") (pintype "passive+no_connect"))
    )
    (net (code "42") (name "unconnected-(U2-NC3-Pad4)") (class "Default")
      (node (ref "U2") (pin "4") (pinfunction "NC3_4") (pintype "passive+no_connect"))
    )
    (net (code "43") (name "unconnected-(U2-NC4-Pad5)") (class "Default")
      (node (ref "U2") (pin "5") (pinfunction "NC4_5") (pintype "passive+no_connect"))
    )
    (net (code "44") (name "unconnected-(U2-NC5-Pad14)") (class "Default")
      (node (ref "U2") (pin "14") (pinfunction "NC5_14") (pintype "passive+no_connect"))
    )
    (net (code "45") (name "unconnected-(U2-NC6-Pad15)") (class "Default")
      (node (ref "U2") (pin "15") (pinfunction "NC6_15") (pintype "passive+no_connect"))
    )
    (net (code "46") (name "unconnected-(U2-NC7-Pad16)") (class "Default")
      (node (ref "U2") (pin "16") (pinfunction "NC7_16") (pintype "passive+no_connect"))
    )
    (net (code "47") (name "unconnected-(U2-NC8-Pad17)") (class "Default")
      (node (ref "U2") (pin "17") (pinfunction "NC8_17") (pintype "passive+no_connect"))
    )
    (net (code "48") (name "unconnected-(U2-RESV1-Pad19)") (class "Default")
      (node (ref "U2") (pin "19") (pinfunction "RESV1_19") (pintype "passive"))
    )
    (net (code "49") (name "unconnected-(U2-RESV2-Pad21)") (class "Default")
      (node (ref "U2") (pin "21") (pinfunction "RESV2_21") (pintype "passive+no_connect"))
    )
    (net (code "50") (name "unconnected-(U4-GPIO6{slash}SDCLK(*){slash}SPI-CLK-Pad20)") (class "Default")
      (node (ref "U4") (pin "20") (pinfunction "GPIO6/SDCLK(*)/SPI-CLK_20") (pintype "passive+no_connect"))
    )
    (net (code "51") (name "unconnected-(U4-GPIO7{slash}SD0(*){slash}SPI-MISO-Pad21)") (class "Default")
      (node (ref "U4") (pin "21") (pinfunction "GPIO7/SD0(*)/SPI-MISO_21") (pintype "passive+no_connect"))
    )
    (net (code "52") (name "unconnected-(U4-GPIO8{slash}SD1(*){slash}SPI-M0SI-Pad22)") (class "Default")
      (node (ref "U4") (pin "22") (pinfunction "GPIO8/SD1(*)/SPI-M0SI_22") (pintype "passive+no_connect"))
    )
    (net (code "53") (name "unconnected-(U4-GPIO9{slash}SD2(*){slash}U1RXD{slash}SPI-HD-Pad17)") (class "Default")
      (node (ref "U4") (pin "17") (pinfunction "GPIO9/SD2(*)/U1RXD/SPI-HD_17") (pintype "passive+no_connect"))
    )
    (net (code "54") (name "unconnected-(U4-GPIO10{slash}SD3(*){slash}U1TXD{slash}SPI-WP-Pad18)") (class "Default")
      (node (ref "U4") (pin "18") (pinfunction "GPIO10/SD3(*)/U1TXD/SPI-WP_18") (pintype "passive+no_connect"))
    )
    (net (code "55") (name "unconnected-(U4-GPIO11{slash}SDCMD(*){slash}SPI-CS0-Pad19)") (class "Default")
      (node (ref "U4") (pin "19") (pinfunction "GPIO11/SDCMD(*)/SPI-CS0_19") (pintype "passive+no_connect"))
    )
    (net (code "56") (name "unconnected-(U4-GPIO12{slash}HSPI-MISO{slash}EMAC_TXD3-Pad14)") (class "Default")
      (node (ref "U4") (pin "14") (pinfunction "GPIO12/HSPI-MISO/EMAC_TXD3_14") (pintype "passive+no_connect"))
    )
    (net (code "57") (name "unconnected-(U4-GPIO13{slash}HSPI-MOSI{slash}EMAC_RX_ER-Pad16)") (class "Default")
      (node (ref "U4") (pin "16") (pinfunction "GPIO13/HSPI-MOSI/EMAC_RX_ER_16") (pintype "passive+no_connect"))
    )
    (net (code "58") (name "unconnected-(U4-GPIO14{slash}HSPI-SCLK{slash}EMAC_TXD2-Pad13)") (class "Default")
      (node (ref "U4") (pin "13") (pinfunction "GPIO14/HSPI-SCLK/EMAC_TXD2_13") (pintype "passive+no_connect"))
    )
    (net (code "59") (name "unconnected-(U4-GPIO17{slash}U2TXD{slash}EMAC_CLK_OUT_180-Pad28)") (class "Default")
      (node (ref "U4") (pin "28") (pinfunction "GPIO17/U2TXD/EMAC_CLK_OUT_180_28") (pintype "passive+no_connect"))
    )
    (net (code "60") (name "unconnected-(U4-GPIO18{slash}VSPI-SCLK-Pad30)") (class "Default")
      (node (ref "U4") (pin "30") (pinfunction "GPIO18/VSPI-SCLK_30") (pintype "passive+no_connect"))
    )
    (net (code "61") (name "unconnected-(U4-GPIO19{slash}VSPI-MISO{slash}EMAC_TXD0-Pad31)") (class "Default")
      (node (ref "U4") (pin "31") (pinfunction "GPIO19/VSPI-MISO/EMAC_TXD0_31") (pintype "passive+no_connect"))
    )
    (net (code "62") (name "unconnected-(U4-GPIO23{slash}VSPI-MOSI-Pad37)") (class "Default")
      (node (ref "U4") (pin "37") (pinfunction "GPIO23/VSPI-MOSI_37") (pintype "passive+no_connect"))
    )
    (net (code "63") (name "unconnected-(U4-GPIO25{slash}EMAC_RXD0-Pad10)") (class "Default")
      (node (ref "U4") (pin "10") (pinfunction "GPIO25/EMAC_RXD0_10") (pintype "passive+no_connect"))
    )
    (net (code "64") (name "unconnected-(U4-GPIO26{slash}EMAC_RXD1-Pad11)") (class "Default")
      (node (ref "U4") (pin "11") (pinfunction "GPIO26/EMAC_RXD1_11") (pintype "passive+no_connect"))
    )
    (net (code "65") (name "unconnected-(U4-GPIO27{slash}EMAC_RX_DV-Pad12)") (class "Default")
      (node (ref "U4") (pin "12") (pinfunction "GPIO27/EMAC_RX_DV_12") (pintype "passive+no_connect"))
    )
    (net (code "66") (name "unconnected-(U4-GPIO32{slash}XTAL_32K_P-Pad8)") (class "Default")
      (node (ref "U4") (pin "8") (pinfunction "GPIO32/XTAL_32K_P_8") (pintype "passive+no_connect"))
    )
    (net (code "67") (name "unconnected-(U4-GPIO33{slash}XTAL_32K_N-Pad9)") (class "Default")
      (node (ref "U4") (pin "9") (pinfunction "GPIO33/XTAL_32K_N_9") (pintype "passive+no_connect"))
    )
    (net (code "68") (name "unconnected-(U4-IO34-Pad6)") (class "Default")
      (node (ref "U4") (pin "6") (pinfunction "IO34_6") (pintype "input+no_connect"))
    )
    (net (code "69") (name "unconnected-(U4-IO35-Pad7)") (class "Default")
      (node (ref "U4") (pin "7") (pinfunction "IO35_7") (pintype "input+no_connect"))
    )
    (net (code "70") (name "unconnected-(U4-IO36{slash}SENSOR_VP-Pad4)") (class "Default")
      (node (ref "U4") (pin "4") (pinfunction "IO36/SENSOR_VP_4") (pintype "input+no_connect"))
    )
    (net (code "71") (name "unconnected-(U4-IO39{slash}SENSOR_VN-Pad5)") (class "Default")
      (node (ref "U4") (pin "5") (pinfunction "IO39/SENSOR_VN_5") (pintype "input+no_connect"))
    )
    (net (code "72") (name "unconnected-(U4-NC-Pad32)") (class "Default")
      (node (ref "U4") (pin "32") (pinfunction "NC_32") (pintype "passive+no_connect"))
    )
  )
)
